# H17R0_Backend.net
KiCad netlist of a schematic drawn in Altium Designer
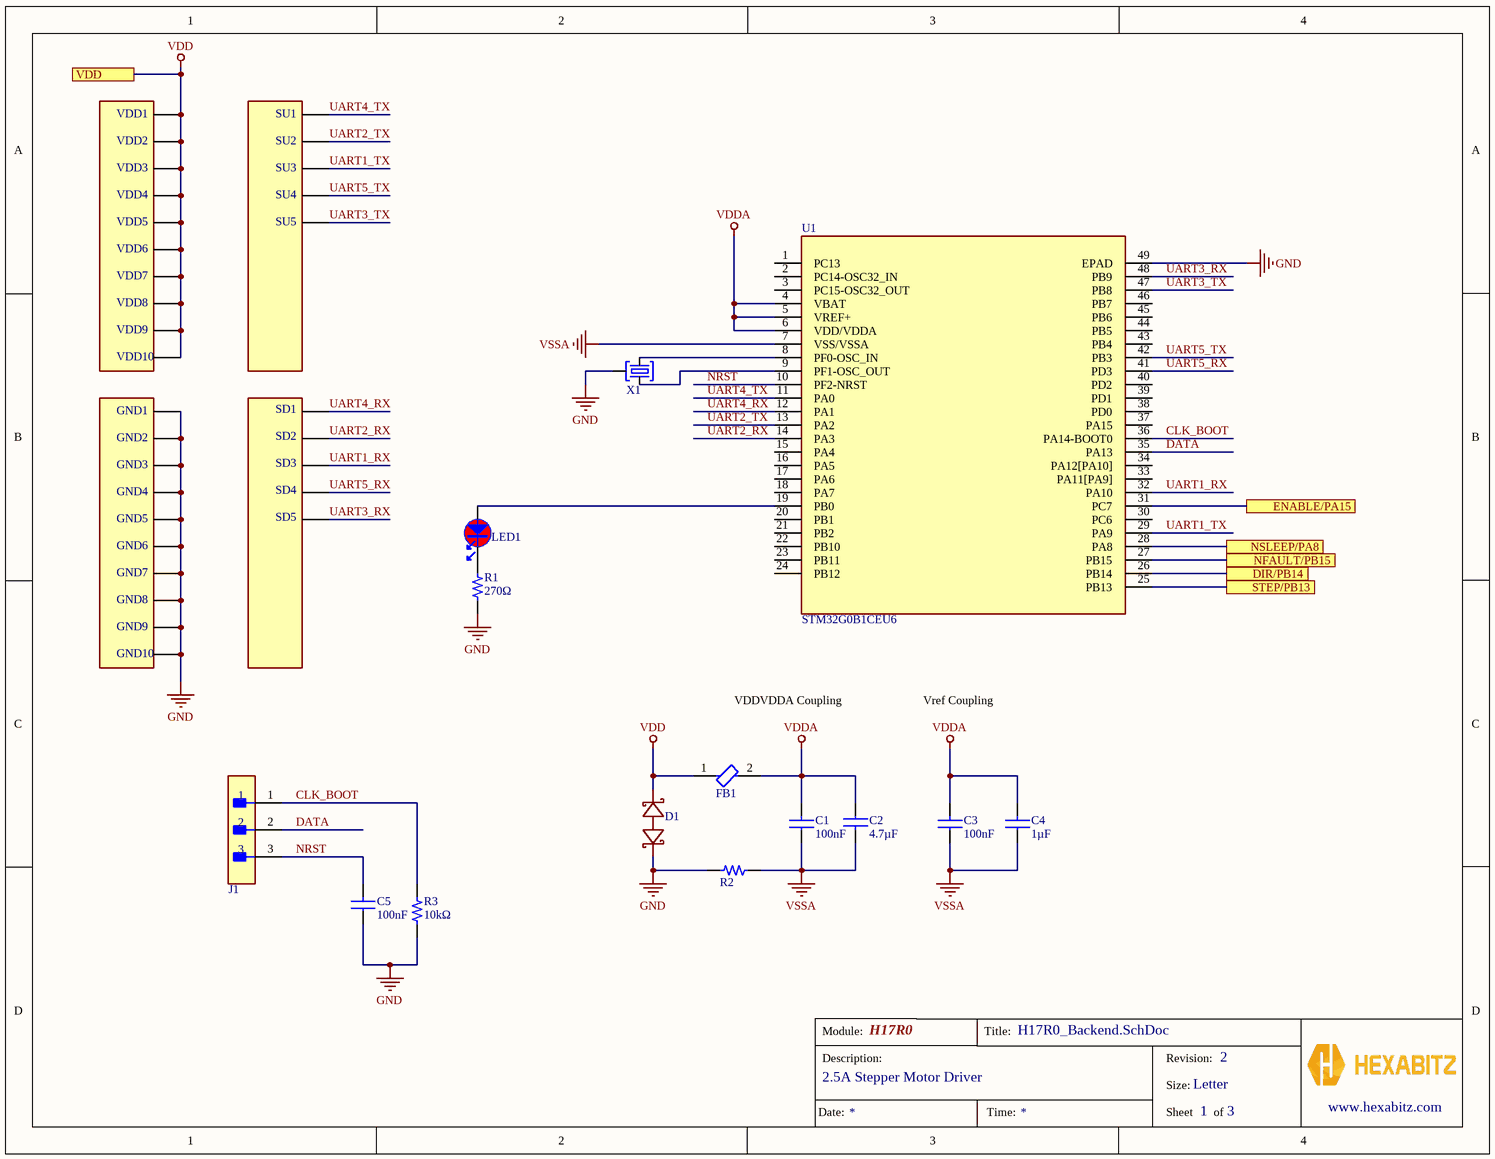
[diagram p0: H17R0_Backend.SchDoc]

(export (version "E")
  (design (tool "Eeschema 10.0.6"))
  (components
    (comp (ref "C1")
      (value "100nF")
      (footprint "C0603")
      (fields
        (field (name "MANUFACTURER") "Samsung Electro-Mechanics")
        (field (name "MANUFACTURER PART NUMBER") "CL10B104KA8NNNC")
        (field (name "TOLERANCE") "10%")
      )
      (libsource (lib "Hexabitz Altium Library") (part "generic Capacitor"))
    )
    (comp (ref "C2")
      (value "4.7µF")
      (footprint "C0805")
      (fields
        (field (name "MANUFACTURER") "Samsung Electro-Mechanics")
        (field (name "MANUFACTURER PART NUMBER") "CL21X475KAQNNNE")
        (field (name "TOLERANCE") "10%")
      )
      (libsource (lib "Hexabitz Altium Library") (part "generic Capacitor"))
    )
    (comp (ref "C3")
      (value "100nF")
      (footprint "C0603")
      (fields
        (field (name "MANUFACTURER") "Samsung Electro-Mechanics")
        (field (name "MANUFACTURER PART NUMBER") "CL10B104KA8NNNC")
        (field (name "TOLERANCE") "10%")
      )
      (libsource (lib "Hexabitz Altium Library") (part "generic Capacitor"))
    )
    (comp (ref "C4")
      (value "1µF")
      (footprint "C0805")
      (description "Ceramic Capacitor, Ceramic, 16V, 10% +Tol, 10% -Tol, X7R, 15% TC, 1uF, Surface Mount, 0805")
      (fields
        (field (name "MANUFACTURER") "Yageo Group")
        (field (name "MANUFACTURER PART NUMBER") "CC0805KKX7R7BB105")
      )
      (libsource (lib "Hexabitz Altium Library") (part "generic Capacitor"))
    )
    (comp (ref "C5")
      (value "100nF")
      (footprint "C0603")
      (fields
        (field (name "MANUFACTURER") "Samsung Electro-Mechanics")
        (field (name "MANUFACTURER PART NUMBER") "CL10B104KA8NNNC")
        (field (name "TOLERANCE") "10%")
      )
      (libsource (lib "Hexabitz Altium Library") (part "generic Capacitor"))
    )
    (comp (ref "D1")
      (value "CDSOD323-T03SC")
      (footprint "SOD2513X114N")
      (description "A 3V, 350W, bi-directional, standard capacitance, SOD323 pkg TVS Diode ¦ Bourns CDSOD323-T03SC")
      (fields (field (name "MANUFACTURER") "Bourns"))
      (libsource (lib "Hexabitz Altium Library") (part "CDSOD323-T03SC"))
    )
    (comp (ref "FB1")
      (value "MMZ1608Y300B")
      (footprint "FP-MMZ1608-0_8-MFG")
      (description "Ferrite Beads 0603 30ohms 1500mA Signal Line AEC-Q200")
      (fields
        (field (name "MANUFACTURER") "TDK")
        (field (name "MANUFACTURER PART NUMBER") "MMZ1608Y300BTD25")
      )
      (libsource (lib "Hexabitz Altium Library") (part "MMZ1608Y300B"))
    )
    (comp (ref "GND1")
      (value "HEXABIT_UART_PORT")
      (footprint "HEXABIT_POWER_PORT_D")
      (libsource (lib "hexabitz_connectors.Library") (part "HEXABIT_POWER_PORT_D"))
    )
    (comp (ref "GND2")
      (value "HEXABIT_UART_PORT")
      (footprint "HEXABIT_POWER_PORT_D")
      (libsource (lib "hexabitz_connectors.Library") (part "HEXABIT_POWER_PORT_D"))
    )
    (comp (ref "GND3")
      (value "HEXABIT_UART_PORT")
      (footprint "HEXABIT_POWER_PORT_D_300R")
      (libsource (lib "hexabitz_connectors.Library") (part "HEXABIT_POWER_PORT_D_300R"))
    )
    (comp (ref "GND4")
      (value "HEXABIT_UART_PORT")
      (footprint "HEXABIT_POWER_PORT_D")
      (libsource (lib "hexabitz_connectors.Library") (part "HEXABIT_POWER_PORT_D"))
    )
    (comp (ref "GND5")
      (value "HEXABIT_UART_PORT")
      (footprint "HEXABIT_POWER_PORT_D")
      (libsource (lib "hexabitz_connectors.Library") (part "HEXABIT_POWER_PORT_D"))
    )
    (comp (ref "GND6")
      (value "HEXABIT_UART_PORT")
      (footprint "HEXABIT_POWER_PORT_D")
      (libsource (lib "hexabitz_connectors.Library") (part "HEXABIT_POWER_PORT_D"))
    )
    (comp (ref "GND7")
      (value "HEXABIT_UART_PORT")
      (footprint "HEXABIT_POWER_PORT_D")
      (libsource (lib "hexabitz_connectors.Library") (part "HEXABIT_POWER_PORT_D"))
    )
    (comp (ref "GND8")
      (value "HEXABIT_UART_PORT")
      (footprint "HEXABIT_POWER_PORT_D_300L")
      (libsource (lib "hexabitz_connectors.Library") (part "HEXABIT_POWER_PORT_D_300L"))
    )
    (comp (ref "GND9")
      (value "HEXABIT_UART_PORT")
      (footprint "HEXABIT_POWER_PORT_D")
      (libsource (lib "hexabitz_connectors.Library") (part "HEXABIT_POWER_PORT_D"))
    )
    (comp (ref "GND10")
      (value "HEXABIT_UART_PORT")
      (footprint "HEXABIT_POWER_PORT_D")
      (libsource (lib "hexabitz_connectors.Library") (part "HEXABIT_POWER_PORT_D"))
    )
    (comp (ref "J1")
      (value "TSW-103-14-G-S")
      (footprint "FP-TSW-103-14-G-S-MFG")
      (description "CONN HEADER VERT 3POS 2.54MM")
      (libsource (lib "Altium Content Vault") (part "cd3439d6ef35ae5d9b27ec4fdd3e828"))
    )
    (comp (ref "LED1")
      (value "VLMS1300-GS08")
      (footprint "FP-6_541-5092_01-4-MFG")
      (description "LED Uni-Color Super Red 639nm 2-Pin Chip 0603(1608Metric) T/R")
      (fields (field (name "MANUFACTURER") "Vishay Semiconductors"))
      (libsource (lib "Hexabitz Altium Library") (part "VLMS1300-GS08"))
    )
    (comp (ref "R1")
      (value "270Ω")
      (footprint "R0603")
      (description "Res Thick Film 0603 270 Ohm 5% 0.1W(1/10W) ±200ppm/C Pad SMD Automotive T/R")
      (fields
        (field (name "MANUFACTURER") "Panasonic")
        (field (name "MANUFACTURER PART NUMBER") "ERJ-3GEYJ271V")
      )
      (libsource (lib "") (part "generic Resistor_2"))
    )
    (comp (ref "R2")
      (value "Manufacturer Part Number")
      (footprint "R0603")
      (libsource (lib "Hexabitz Altium Library") (part "generic Resistor"))
    )
    (comp (ref "R3")
      (value "10kΩ")
      (footprint "R0603")
      (description "100mW Thick Film Resistors ±100ppm/℃ ±1% 10kΩ 0603 Chip Resistor - Surface Mount ROHS")
      (fields
        (field (name "MANUFACTURER") "Yageo Group")
        (field (name "MANUFACTURER PART NUMBER") "RC0603FR-0710KL")
      )
      (libsource (lib "") (part "generic Resistor_1"))
    )
    (comp (ref "SD1")
      (value "HEXABIT_UART_PORT")
      (footprint "HEXABIT_UART_PORT_D")
      (libsource (lib "hexabitz_connectors.Library") (part "HEXABIT_UART_PORT_D"))
    )
    (comp (ref "SD2")
      (value "HEXABIT_UART_PORT")
      (footprint "HEXABIT_UART_PORT_D")
      (libsource (lib "hexabitz_connectors.Library") (part "HEXABIT_UART_PORT_D"))
    )
    (comp (ref "SD3")
      (value "HEXABIT_UART_PORT")
      (footprint "HEXABIT_UART_PORT_D")
      (libsource (lib "hexabitz_connectors.Library") (part "HEXABIT_UART_PORT_D"))
    )
    (comp (ref "SD4")
      (value "HEXABIT_UART_PORT")
      (footprint "HEXABIT_UART_PORT_D")
      (libsource (lib "hexabitz_connectors.Library") (part "HEXABIT_UART_PORT_D"))
    )
    (comp (ref "SD5")
      (value "HEXABIT_UART_PORT")
      (footprint "HEXABIT_UART_PORT_D")
      (libsource (lib "hexabitz_connectors.Library") (part "HEXABIT_UART_PORT_D"))
    )
    (comp (ref "SU1")
      (value "HEXABIT_UART_PORT")
      (footprint "HEXABIT_UART_PORT_U")
      (libsource (lib "hexabitz_connectors.Library") (part "HEXABIT_UART_PORT_U"))
    )
    (comp (ref "SU2")
      (value "HEXABIT_UART_PORT")
      (footprint "HEXABIT_UART_PORT_U")
      (libsource (lib "hexabitz_connectors.Library") (part "HEXABIT_UART_PORT_U"))
    )
    (comp (ref "SU3")
      (value "HEXABIT_UART_PORT")
      (footprint "HEXABIT_UART_PORT_U")
      (libsource (lib "hexabitz_connectors.Library") (part "HEXABIT_UART_PORT_U"))
    )
    (comp (ref "SU4")
      (value "HEXABIT_UART_PORT")
      (footprint "HEXABIT_UART_PORT_U")
      (libsource (lib "hexabitz_connectors.Library") (part "HEXABIT_UART_PORT_U"))
    )
    (comp (ref "SU5")
      (value "HEXABIT_UART_PORT")
      (footprint "HEXABIT_UART_PORT_U")
      (libsource (lib "hexabitz_connectors.Library") (part "HEXABIT_UART_PORT_U"))
    )
    (comp (ref "U1")
      (value "STM32G0B1CEU6")
      (footprint "QFN50P700X700X65-49N-D")
      (description "MCU 32-bit ARM Cortex M0+ RISC 512KB Flash 1.8V/2.5V/3.3V 48-Pin UFQFPN EP Tray")
      (fields
        (field (name "MANUFACTURER") "STMicroelectronics")
        (field (name "MANUFACTURER PART NUMBER") "STM32G0B1CEU6")
      )
      (libsource (lib "Hexabitz Altium Library") (part "STM32G0B1CEU6"))
    )
    (comp (ref "VDD1")
      (value "HEXABIT_UART_PORT")
      (footprint "HEXABIT_POWER_PORT_U")
      (libsource (lib "hexabitz_connectors.Library") (part "HEXABIT_POWER_PORT_U"))
    )
    (comp (ref "VDD2")
      (value "HEXABIT_UART_PORT")
      (footprint "HEXABIT_POWER_PORT_U")
      (libsource (lib "hexabitz_connectors.Library") (part "HEXABIT_POWER_PORT_U"))
    )
    (comp (ref "VDD3")
      (value "HEXABIT_UART_PORT")
      (footprint "HEXABIT_POWER_PORT_U_300R")
      (libsource (lib "hexabitz_connectors.Library") (part "HEXABIT_POWER_PORT_U_300R"))
    )
    (comp (ref "VDD4")
      (value "HEXABIT_UART_PORT")
      (footprint "HEXABIT_POWER_PORT_U")
      (libsource (lib "hexabitz_connectors.Library") (part "HEXABIT_POWER_PORT_U"))
    )
    (comp (ref "VDD5")
      (value "HEXABIT_UART_PORT")
      (footprint "HEXABIT_POWER_PORT_U")
      (libsource (lib "hexabitz_connectors.Library") (part "HEXABIT_POWER_PORT_U"))
    )
    (comp (ref "VDD6")
      (value "HEXABIT_UART_PORT")
      (footprint "HEXABIT_POWER_PORT_U")
      (libsource (lib "hexabitz_connectors.Library") (part "HEXABIT_POWER_PORT_U"))
    )
    (comp (ref "VDD7")
      (value "HEXABIT_UART_PORT")
      (footprint "HEXABIT_POWER_PORT_U")
      (libsource (lib "hexabitz_connectors.Library") (part "HEXABIT_POWER_PORT_U"))
    )
    (comp (ref "VDD8")
      (value "HEXABIT_UART_PORT")
      (footprint "HEXABIT_POWER_PORT_U_300L")
      (libsource (lib "hexabitz_connectors.Library") (part "HEXABIT_POWER_PORT_U_300L"))
    )
    (comp (ref "VDD9")
      (value "HEXABIT_UART_PORT")
      (footprint "HEXABIT_POWER_PORT_U")
      (libsource (lib "hexabitz_connectors.Library") (part "HEXABIT_POWER_PORT_U"))
    )
    (comp (ref "VDD10")
      (value "HEXABIT_UART_PORT")
      (footprint "HEXABIT_POWER_PORT_U")
      (libsource (lib "hexabitz_connectors.Library") (part "HEXABIT_POWER_PORT_U"))
    )
    (comp (ref "X1")
      (value "CSTCE8M00G52Z-R0")
      (footprint "XTALL_CSTCE8M00G52")
      (description "Ceramic Resonator 8MHz ±0.5% (Tol) ±0.2% (Stability) 10pF 40Ohm 3-Pin CSMD T/R")
      (fields (field (name "MANUFACTURER") "Murata") (field (name "TOLERANCE") "0.5%"))
      (libsource (lib "Hexabitz Altium Library") (part "CSTCE8M00G52Z-R0"))
    )
  )
  (nets
    (net (code "1") (name "/CLK_BOOT") (class "Default")
      (node (ref "J1") (pin "1") (pinfunction "1_1") (pintype "passive"))
      (node (ref "R3") (pin "1") (pinfunction "1_1") (pintype "passive"))
      (node (ref "U1") (pin "36") (pinfunction "PA14-BOOT0_36") (pintype "passive"))
    )
    (net (code "2") (name "/DATA") (class "Default")
      (node (ref "J1") (pin "2") (pinfunction "2_2") (pintype "passive"))
      (node (ref "U1") (pin "35") (pinfunction "PA13_35") (pintype "passive"))
    )
    (net (code "3") (name "/DIR{slash}PB14") (class "Default")
      (node (ref "U1") (pin "26") (pinfunction "PB14_26") (pintype "passive"))
    )
    (net (code "4") (name "/ENABLE{slash}PA15") (class "Default")
      (node (ref "U1") (pin "31") (pinfunction "PC7_31") (pintype "passive"))
    )
    (net (code "5") (name "/NFAULT{slash}PB15") (class "Default")
      (node (ref "U1") (pin "27") (pinfunction "PB15_27") (pintype "passive"))
    )
    (net (code "6") (name "/NRST") (class "Default")
      (node (ref "C5") (pin "2") (pinfunction "2_2") (pintype "passive"))
      (node (ref "J1") (pin "3") (pinfunction "3_3") (pintype "passive"))
      (node (ref "U1") (pin "10") (pinfunction "PF2-NRST_10") (pintype "passive"))
    )
    (net (code "7") (name "/NSLEEP{slash}PA8") (class "Default")
      (node (ref "U1") (pin "28") (pinfunction "PA8_28") (pintype "passive"))
    )
    (net (code "8") (name "/STEP{slash}PB13") (class "Default")
      (node (ref "U1") (pin "25") (pinfunction "PB13_25") (pintype "passive"))
    )
    (net (code "9") (name "/UART1_RX") (class "Default")
      (node (ref "SD3") (pin "UART_D") (pinfunction "UART_D_UART_D") (pintype "passive"))
      (node (ref "U1") (pin "32") (pinfunction "PA10_32") (pintype "passive"))
    )
    (net (code "10") (name "/UART1_TX") (class "Default")
      (node (ref "SU3") (pin "UART_U") (pinfunction "UART_U_UART_U") (pintype "passive"))
      (node (ref "U1") (pin "29") (pinfunction "PA9_29") (pintype "passive"))
    )
    (net (code "11") (name "/UART2_RX") (class "Default")
      (node (ref "SD2") (pin "UART_D") (pinfunction "UART_D_UART_D") (pintype "passive"))
      (node (ref "U1") (pin "14") (pinfunction "PA3_14") (pintype "passive"))
    )
    (net (code "12") (name "/UART2_TX") (class "Default")
      (node (ref "SU2") (pin "UART_U") (pinfunction "UART_U_UART_U") (pintype "passive"))
      (node (ref "U1") (pin "13") (pinfunction "PA2_13") (pintype "passive"))
    )
    (net (code "13") (name "/UART3_RX") (class "Default")
      (node (ref "SD5") (pin "UART_D") (pinfunction "UART_D_UART_D") (pintype "passive"))
      (node (ref "U1") (pin "48") (pinfunction "PB9_48") (pintype "passive"))
    )
    (net (code "14") (name "/UART3_TX") (class "Default")
      (node (ref "SU5") (pin "UART_U") (pinfunction "UART_U_UART_U") (pintype "passive"))
      (node (ref "U1") (pin "47") (pinfunction "PB8_47") (pintype "passive"))
    )
    (net (code "15") (name "/UART4_RX") (class "Default")
      (node (ref "SD1") (pin "UART_D") (pinfunction "UART_D_UART_D") (pintype "passive"))
      (node (ref "U1") (pin "12") (pinfunction "PA1_12") (pintype "passive"))
    )
    (net (code "16") (name "/UART4_TX") (class "Default")
      (node (ref "SU1") (pin "UART_U") (pinfunction "UART_U_UART_U") (pintype "passive"))
      (node (ref "U1") (pin "11") (pinfunction "PA0_11") (pintype "passive"))
    )
    (net (code "17") (name "/UART5_RX") (class "Default")
      (node (ref "SD4") (pin "UART_D") (pinfunction "UART_D_UART_D") (pintype "passive"))
      (node (ref "U1") (pin "41") (pinfunction "PD3_41") (pintype "passive"))
    )
    (net (code "18") (name "/UART5_TX") (class "Default")
      (node (ref "SU4") (pin "UART_U") (pinfunction "UART_U_UART_U") (pintype "passive"))
      (node (ref "U1") (pin "42") (pinfunction "PB3_42") (pintype "passive"))
    )
    (net (code "19") (name "GND") (class "Default")
      (node (ref "C5") (pin "1") (pinfunction "1_1") (pintype "passive"))
      (node (ref "D1") (pin "1") (pinfunction "A_1") (pintype "passive"))
      (node (ref "GND1") (pin "Pwr_D") (pinfunction "Pwr_D_Pwr_D") (pintype "passive"))
      (node (ref "GND10") (pin "Pwr_D") (pinfunction "Pwr_D_Pwr_D") (pintype "passive"))
      (node (ref "GND2") (pin "Pwr_D") (pinfunction "Pwr_D_Pwr_D") (pintype "passive"))
      (node (ref "GND3") (pin "Pwr_D") (pinfunction "Pwr_D_Pwr_D") (pintype "passive"))
      (node (ref "GND4") (pin "Pwr_D") (pinfunction "Pwr_D_Pwr_D") (pintype "passive"))
      (node (ref "GND5") (pin "Pwr_D") (pinfunction "Pwr_D_Pwr_D") (pintype "passive"))
      (node (ref "GND6") (pin "Pwr_D") (pinfunction "Pwr_D_Pwr_D") (pintype "passive"))
      (node (ref "GND7") (pin "Pwr_D") (pinfunction "Pwr_D_Pwr_D") (pintype "passive"))
      (node (ref "GND8") (pin "Pwr_D") (pinfunction "Pwr_D_Pwr_D") (pintype "passive"))
      (node (ref "GND9") (pin "Pwr_D") (pinfunction "Pwr_D_Pwr_D") (pintype "passive"))
      (node (ref "R1") (pin "1") (pinfunction "1_1") (pintype "passive"))
      (node (ref "R2") (pin "1") (pinfunction "1_1") (pintype "passive"))
      (node (ref "R3") (pin "2") (pinfunction "2_2") (pintype "passive"))
      (node (ref "U1") (pin "49") (pinfunction "EPAD_49") (pintype "passive"))
      (node (ref "X1") (pin "P$2") (pinfunction "2_P$2") (pintype "passive"))
    )
    (net (code "20") (name "Net-(LED1-Pad1)") (class "Default")
      (node (ref "LED1") (pin "1") (pintype "passive"))
      (node (ref "R1") (pin "2") (pinfunction "2_2") (pintype "passive"))
    )
    (net (code "21") (name "Net-(U1-PB0)") (class "Default")
      (node (ref "LED1") (pin "2") (pintype "passive"))
      (node (ref "U1") (pin "19") (pinfunction "PB0_19") (pintype "passive"))
    )
    (net (code "22") (name "Net-(U1-PF0-OSC_IN)") (class "Default")
      (node (ref "U1") (pin "8") (pinfunction "PF0-OSC_IN_8") (pintype "passive"))
      (node (ref "X1") (pin "P$3") (pinfunction "3_P$3") (pintype "passive"))
    )
    (net (code "23") (name "Net-(U1-PF1-OSC_OUT)") (class "Default")
      (node (ref "U1") (pin "9") (pinfunction "PF1-OSC_OUT_9") (pintype "passive"))
      (node (ref "X1") (pin "P$1") (pinfunction "1_P$1") (pintype "passive"))
    )
    (net (code "24") (name "VDD") (class "Default")
      (node (ref "D1") (pin "2") (pinfunction "C_2") (pintype "passive"))
      (node (ref "FB1") (pin "1") (pinfunction "1_1") (pintype "passive"))
      (node (ref "VDD1") (pin "Pwr_U") (pinfunction "Pwr_U_Pwr_U") (pintype "passive"))
      (node (ref "VDD10") (pin "Pwr_U") (pinfunction "Pwr_U_Pwr_U") (pintype "passive"))
      (node (ref "VDD2") (pin "Pwr_U") (pinfunction "Pwr_U_Pwr_U") (pintype "passive"))
      (node (ref "VDD3") (pin "Pwr_U") (pinfunction "Pwr_U_Pwr_U") (pintype "passive"))
      (node (ref "VDD4") (pin "Pwr_U") (pinfunction "Pwr_U_Pwr_U") (pintype "passive"))
      (node (ref "VDD5") (pin "Pwr_U") (pinfunction "Pwr_U_Pwr_U") (pintype "passive"))
      (node (ref "VDD6") (pin "Pwr_U") (pinfunction "Pwr_U_Pwr_U") (pintype "passive"))
      (node (ref "VDD7") (pin "Pwr_U") (pinfunction "Pwr_U_Pwr_U") (pintype "passive"))
      (node (ref "VDD8") (pin "Pwr_U") (pinfunction "Pwr_U_Pwr_U") (pintype "passive"))
      (node (ref "VDD9") (pin "Pwr_U") (pinfunction "Pwr_U_Pwr_U") (pintype "passive"))
    )
    (net (code "25") (name "VDDA") (class "Default")
      (node (ref "C1") (pin "2") (pinfunction "2_2") (pintype "passive"))
      (node (ref "C2") (pin "1") (pinfunction "1_1") (pintype "passive"))
      (node (ref "C3") (pin "2") (pinfunction "2_2") (pintype "passive"))
      (node (ref "C4") (pin "2") (pinfunction "2_2") (pintype "passive"))
      (node (ref "FB1") (pin "2") (pinfunction "2_2") (pintype "passive"))
      (node (ref "U1") (pin "4") (pinfunction "VBAT_4") (pintype "passive"))
      (node (ref "U1") (pin "5") (pinfunction "VREF+_5") (pintype "passive"))
      (node (ref "U1") (pin "6") (pinfunction "VDD/VDDA_6") (pintype "passive"))
    )
    (net (code "26") (name "VSSA") (class "Default")
      (node (ref "C1") (pin "1") (pinfunction "1_1") (pintype "passive"))
      (node (ref "C2") (pin "2") (pinfunction "2_2") (pintype "passive"))
      (node (ref "C3") (pin "1") (pinfunction "1_1") (pintype "passive"))
      (node (ref "C4") (pin "1") (pinfunction "1_1") (pintype "passive"))
      (node (ref "R2") (pin "2") (pinfunction "2_2") (pintype "passive"))
      (node (ref "U1") (pin "7") (pinfunction "VSS/VSSA_7") (pintype "passive"))
    )
    (net (code "27") (name "unconnected-(U1-PA4-Pad15)") (class "Default")
      (node (ref "U1") (pin "15") (pinfunction "PA4_15") (pintype "passive"))
    )
    (net (code "28") (name "unconnected-(U1-PA5-Pad16)") (class "Default")
      (node (ref "U1") (pin "16") (pinfunction "PA5_16") (pintype "passive"))
    )
    (net (code "29") (name "unconnected-(U1-PA6-Pad17)") (class "Default")
      (node (ref "U1") (pin "17") (pinfunction "PA6_17") (pintype "passive"))
    )
    (net (code "30") (name "unconnected-(U1-PA7-Pad18)") (class "Default")
      (node (ref "U1") (pin "18") (pinfunction "PA7_18") (pintype "passive"))
    )
    (net (code "31") (name "unconnected-(U1-PA11[PA9]-Pad33)") (class "Default")
      (node (ref "U1") (pin "33") (pinfunction "PA11[PA9]_33") (pintype "passive"))
    )
    (net (code "32") (name "unconnected-(U1-PA12[PA10]-Pad34)") (class "Default")
      (node (ref "U1") (pin "34") (pinfunction "PA12[PA10]_34") (pintype "passive"))
    )
    (net (code "33") (name "unconnected-(U1-PA15-Pad37)") (class "Default")
      (node (ref "U1") (pin "37") (pinfunction "PA15_37") (pintype "passive"))
    )
    (net (code "34") (name "unconnected-(U1-PB1-Pad20)") (class "Default")
      (node (ref "U1") (pin "20") (pinfunction "PB1_20") (pintype "passive"))
    )
    (net (code "35") (name "unconnected-(U1-PB2-Pad21)") (class "Default")
      (node (ref "U1") (pin "21") (pinfunction "PB2_21") (pintype "passive"))
    )
    (net (code "36") (name "unconnected-(U1-PB4-Pad43)") (class "Default")
      (node (ref "U1") (pin "43") (pinfunction "PB4_43") (pintype "passive"))
    )
    (net (code "37") (name "unconnected-(U1-PB5-Pad44)") (class "Default")
      (node (ref "U1") (pin "44") (pinfunction "PB5_44") (pintype "passive"))
    )
    (net (code "38") (name "unconnected-(U1-PB6-Pad45)") (class "Default")
      (node (ref "U1") (pin "45") (pinfunction "PB6_45") (pintype "passive"))
    )
    (net (code "39") (name "unconnected-(U1-PB7-Pad46)") (class "Default")
      (node (ref "U1") (pin "46") (pinfunction "PB7_46") (pintype "passive"))
    )
    (net (code "40") (name "unconnected-(U1-PB10-Pad22)") (class "Default")
      (node (ref "U1") (pin "22") (pinfunction "PB10_22") (pintype "passive"))
    )
    (net (code "41") (name "unconnected-(U1-PB11-Pad23)") (class "Default")
      (node (ref "U1") (pin "23") (pinfunction "PB11_23") (pintype "passive"))
    )
    (net (code "42") (name "unconnected-(U1-PB12-Pad24)") (class "Default")
      (node (ref "U1") (pin "24") (pinfunction "PB12_24") (pintype "passive"))
    )
    (net (code "43") (name "unconnected-(U1-PC6-Pad30)") (class "Default")
      (node (ref "U1") (pin "30") (pinfunction "PC6_30") (pintype "passive"))
    )
    (net (code "44") (name "unconnected-(U1-PC13-Pad1)") (class "Default")
      (node (ref "U1") (pin "1") (pinfunction "PC13_1") (pintype "passive"))
    )
    (net (code "45") (name "unconnected-(U1-PC14-OSC32_IN-Pad2)") (class "Default")
      (node (ref "U1") (pin "2") (pinfunction "PC14-OSC32_IN_2") (pintype "passive"))
    )
    (net (code "46") (name "unconnected-(U1-PC15-OSC32_OUT-Pad3)") (class "Default")
      (node (ref "U1") (pin "3") (pinfunction "PC15-OSC32_OUT_3") (pintype "passive"))
    )
    (net (code "47") (name "unconnected-(U1-PD0-Pad38)") (class "Default")
      (node (ref "U1") (pin "38") (pinfunction "PD0_38") (pintype "passive"))
    )
    (net (code "48") (name "unconnected-(U1-PD1-Pad39)") (class "Default")
      (node (ref "U1") (pin "39") (pinfunction "PD1_39") (pintype "passive"))
    )
    (net (code "49") (name "unconnected-(U1-PD2-Pad40)") (class "Default")
      (node (ref "U1") (pin "40") (pinfunction "PD2_40") (pintype "passive"))
    )
  )
)
